# incandescentDriver.net
KiCad netlist of a schematic drawn in EAGLE
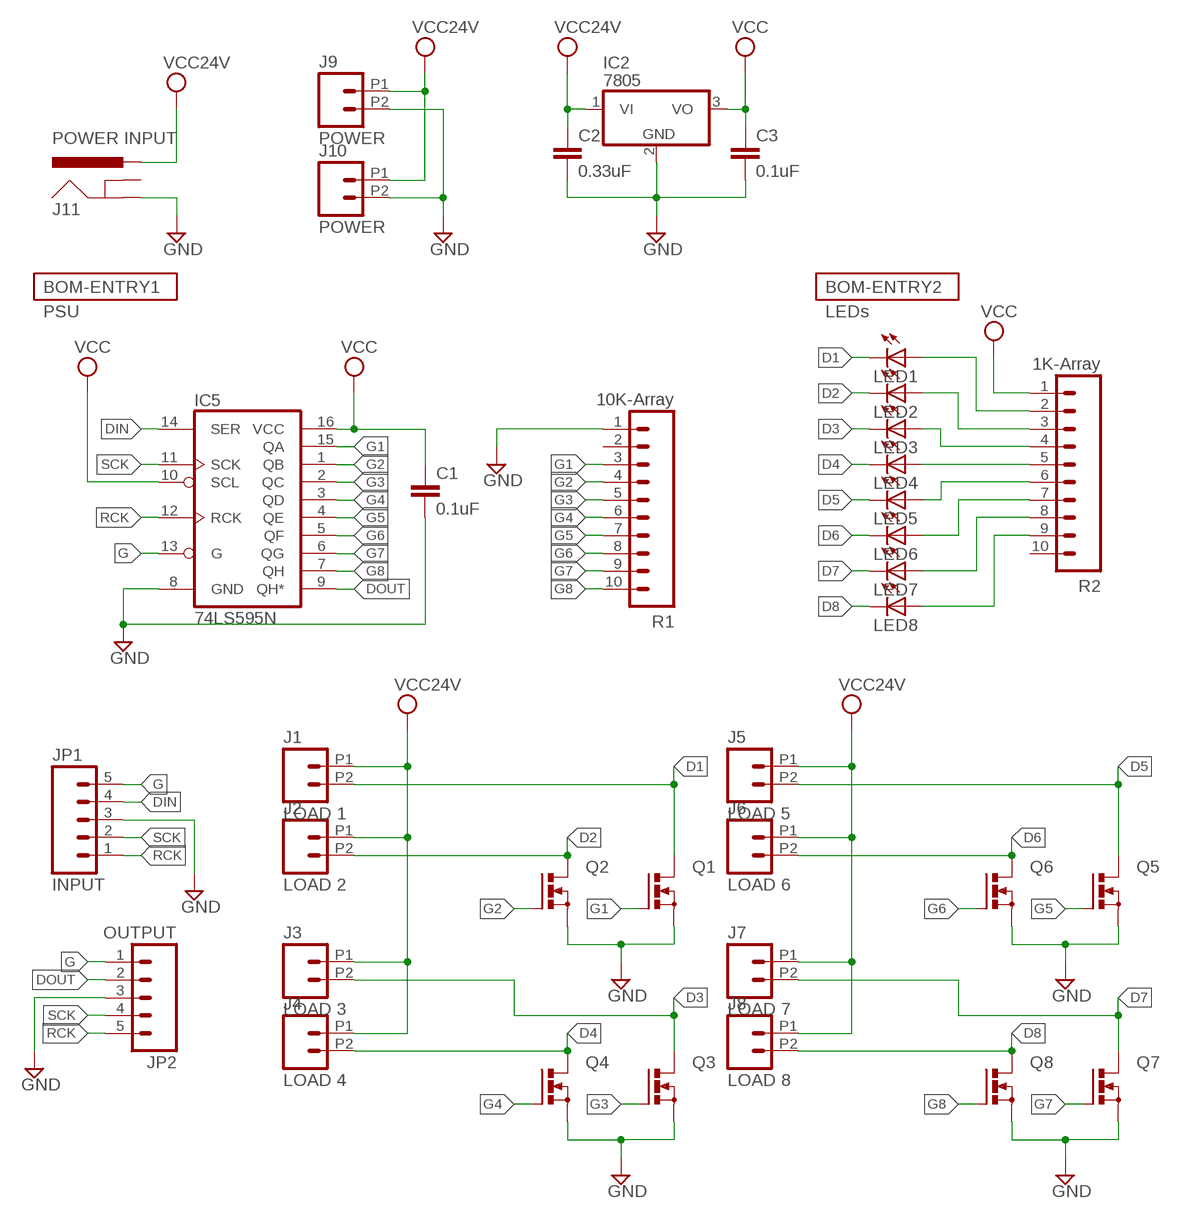
[diagram p0: schematic, sheet 1]

(export (version "E")
  (design (tool "Eeschema 10.0.6"))
  (components
    (comp (ref "C1")
      (value "0.1uF")
      (footprint "eagle-import:CAP-PTH-SMALL")
      (fields (field (name "PARTNO") "SR295E104MAR"))
      (libsource (lib "eagle-import") (part "CAPPTH"))
    )
    (comp (ref "C2")
      (value "0.33uF")
      (footprint "eagle-import:CAP-PTH-SMALL")
      (fields (field (name "PARTNO") "FK24X7R1H334K"))
      (libsource (lib "eagle-import") (part "CAPPTH"))
    )
    (comp (ref "C3")
      (value "0.1uF")
      (footprint "eagle-import:CAP-PTH-SMALL")
      (fields (field (name "PARTNO") "SR295E104MAR"))
      (libsource (lib "eagle-import") (part "CAPPTH"))
    )
    (comp (ref "IC2")
      (value "7805")
      (footprint "eagle-import:TO220V")
      (fields (field (name "PARTNO") "NCP7805TG"))
      (libsource (lib "eagle-import") (part "78TV8"))
    )
    (comp (ref "IC5")
      (value "74LS595N")
      (footprint "eagle-import:DIL16")
      (fields (field (name "PARTNO") "SN74HC164N"))
      (libsource (lib "eagle-import") (part "74595NLS"))
    )
    (comp (ref "J1")
      (value "LOAD 1")
      (footprint "eagle-import:1X02-5.08-SCREWTERM")
      (fields (field (name "PARTNO") "OSTTC022162"))
      (libsource (lib "eagle-import") (part "HEADER"))
    )
    (comp (ref "J2")
      (value "LOAD 2")
      (footprint "eagle-import:1X02-5.08-SCREWTERM")
      (fields (field (name "PARTNO") "OSTTC022162"))
      (libsource (lib "eagle-import") (part "HEADER"))
    )
    (comp (ref "J3")
      (value "LOAD 3")
      (footprint "eagle-import:1X02-5.08-SCREWTERM")
      (fields (field (name "PARTNO") "OSTTC022162"))
      (libsource (lib "eagle-import") (part "HEADER"))
    )
    (comp (ref "J4")
      (value "LOAD 4")
      (footprint "eagle-import:1X02-5.08-SCREWTERM")
      (fields (field (name "PARTNO") "OSTTC022162"))
      (libsource (lib "eagle-import") (part "HEADER"))
    )
    (comp (ref "J5")
      (value "LOAD 5")
      (footprint "eagle-import:1X02-5.08-SCREWTERM")
      (fields (field (name "PARTNO") "OSTTC022162"))
      (libsource (lib "eagle-import") (part "HEADER"))
    )
    (comp (ref "J6")
      (value "LOAD 6")
      (footprint "eagle-import:1X02-5.08-SCREWTERM")
      (fields (field (name "PARTNO") "OSTTC022162"))
      (libsource (lib "eagle-import") (part "HEADER"))
    )
    (comp (ref "J7")
      (value "LOAD 7")
      (footprint "eagle-import:1X02-5.08-SCREWTERM")
      (fields (field (name "PARTNO") "OSTTC022162"))
      (libsource (lib "eagle-import") (part "HEADER"))
    )
    (comp (ref "J8")
      (value "LOAD 8")
      (footprint "eagle-import:1X02-5.08-SCREWTERM")
      (fields (field (name "PARTNO") "OSTTC022162"))
      (libsource (lib "eagle-import") (part "HEADER"))
    )
    (comp (ref "J9")
      (value "POWER")
      (footprint "eagle-import:1X02-5.08-SCREWTERM")
      (fields (field (name "PARTNO") "OSTTC022162"))
      (libsource (lib "eagle-import") (part "HEADER"))
    )
    (comp (ref "J10")
      (value "POWER")
      (footprint "eagle-import:1X02-5.08-SCREWTERM")
      (fields (field (name "PARTNO") "OSTTC022162"))
      (libsource (lib "eagle-import") (part "HEADER"))
    )
    (comp (ref "J11")
      (value "POWER INPUT")
      (footprint "eagle-import:POWER_JACK_PTH_LOCK")
      (fields (field (name "PARTNO") "PJ-202A"))
      (libsource (lib "eagle-import") (part "POWER_JACKPTH_LOCK"))
    )
    (comp (ref "JP1")
      (value "INPUT")
      (footprint "eagle-import:1X05_LOCK")
      (fields (field (name "PARTNO") "M20-9960545"))
      (libsource (lib "eagle-import") (part "M05LOCK"))
    )
    (comp (ref "JP2")
      (value "OUTPUT")
      (footprint "eagle-import:1X05_LOCK")
      (fields (field (name "PARTNO") "M20-9960545"))
      (libsource (lib "eagle-import") (part "M05LOCK"))
    )
    (comp (ref "LED1")
      (value "LED5MM")
      (footprint "eagle-import:LED5MM")
      (libsource (lib "eagle-import") (part "LED5MM"))
    )
    (comp (ref "LED2")
      (value "LED5MM")
      (footprint "eagle-import:LED5MM")
      (libsource (lib "eagle-import") (part "LED5MM"))
    )
    (comp (ref "LED3")
      (value "LED5MM")
      (footprint "eagle-import:LED5MM")
      (libsource (lib "eagle-import") (part "LED5MM"))
    )
    (comp (ref "LED4")
      (value "LED5MM")
      (footprint "eagle-import:LED5MM")
      (libsource (lib "eagle-import") (part "LED5MM"))
    )
    (comp (ref "LED5")
      (value "LED5MM")
      (footprint "eagle-import:LED5MM")
      (libsource (lib "eagle-import") (part "LED5MM"))
    )
    (comp (ref "LED6")
      (value "LED5MM")
      (footprint "eagle-import:LED5MM")
      (libsource (lib "eagle-import") (part "LED5MM"))
    )
    (comp (ref "LED7")
      (value "LED5MM")
      (footprint "eagle-import:LED5MM")
      (libsource (lib "eagle-import") (part "LED5MM"))
    )
    (comp (ref "LED8")
      (value "LED5MM")
      (footprint "eagle-import:LED5MM")
      (libsource (lib "eagle-import") (part "LED5MM"))
    )
    (comp (ref "Q1")
      (value "PMOSFET_NTO220BV")
      (footprint "eagle-import:TO220BV")
      (fields (field (name "PARTNO") "FQP13N10L"))
      (libsource (lib "eagle-import") (part "PMOSFET_NTO220BV"))
    )
    (comp (ref "Q2")
      (value "PMOSFET_NTO220BV")
      (footprint "eagle-import:TO220BV")
      (fields (field (name "PARTNO") "FQP13N10L"))
      (libsource (lib "eagle-import") (part "PMOSFET_NTO220BV"))
    )
    (comp (ref "Q3")
      (value "PMOSFET_NTO220BV")
      (footprint "eagle-import:TO220BV")
      (fields (field (name "PARTNO") "FQP13N10L"))
      (libsource (lib "eagle-import") (part "PMOSFET_NTO220BV"))
    )
    (comp (ref "Q4")
      (value "PMOSFET_NTO220BV")
      (footprint "eagle-import:TO220BV")
      (fields (field (name "PARTNO") "FQP13N10L"))
      (libsource (lib "eagle-import") (part "PMOSFET_NTO220BV"))
    )
    (comp (ref "Q5")
      (value "PMOSFET_NTO220BV")
      (footprint "eagle-import:TO220BV")
      (fields (field (name "PARTNO") "FQP13N10L"))
      (libsource (lib "eagle-import") (part "PMOSFET_NTO220BV"))
    )
    (comp (ref "Q6")
      (value "PMOSFET_NTO220BV")
      (footprint "eagle-import:TO220BV")
      (fields (field (name "PARTNO") "FQP13N10L"))
      (libsource (lib "eagle-import") (part "PMOSFET_NTO220BV"))
    )
    (comp (ref "Q7")
      (value "PMOSFET_NTO220BV")
      (footprint "eagle-import:TO220BV")
      (fields (field (name "PARTNO") "FQP13N10L"))
      (libsource (lib "eagle-import") (part "PMOSFET_NTO220BV"))
    )
    (comp (ref "Q8")
      (value "PMOSFET_NTO220BV")
      (footprint "eagle-import:TO220BV")
      (fields (field (name "PARTNO") "FQP13N10L"))
      (libsource (lib "eagle-import") (part "PMOSFET_NTO220BV"))
    )
    (comp (ref "R1")
      (value "10K-Array")
      (footprint "eagle-import:1X10_LOCK")
      (fields (field (name "PARTNO") "L101S103LF"))
      (libsource (lib "eagle-import") (part "M10LOCK"))
    )
    (comp (ref "R2")
      (value "1K-Array")
      (footprint "eagle-import:1X10_LOCK")
      (fields (field (name "PARTNO") "4609X-101-102LF"))
      (libsource (lib "eagle-import") (part "M10LOCK"))
    )
  )
  (nets
    (net (code "1") (name "D1") (class "Default")
      (node (ref "J1") (pin "P2") (pinfunction "1_P2") (pintype "passive"))
      (node (ref "LED1") (pin "K") (pinfunction "C_K") (pintype "passive"))
      (node (ref "Q1") (pin "D") (pinfunction "D_D") (pintype "passive"))
    )
    (net (code "2") (name "D2") (class "Default")
      (node (ref "J2") (pin "P2") (pinfunction "1_P2") (pintype "passive"))
      (node (ref "LED2") (pin "K") (pinfunction "C_K") (pintype "passive"))
      (node (ref "Q2") (pin "D") (pinfunction "D_D") (pintype "passive"))
    )
    (net (code "3") (name "D3") (class "Default")
      (node (ref "J3") (pin "P2") (pinfunction "1_P2") (pintype "passive"))
      (node (ref "LED3") (pin "K") (pinfunction "C_K") (pintype "passive"))
      (node (ref "Q3") (pin "D") (pinfunction "D_D") (pintype "passive"))
    )
    (net (code "4") (name "D4") (class "Default")
      (node (ref "J4") (pin "P2") (pinfunction "1_P2") (pintype "passive"))
      (node (ref "LED4") (pin "K") (pinfunction "C_K") (pintype "passive"))
      (node (ref "Q4") (pin "D") (pinfunction "D_D") (pintype "passive"))
    )
    (net (code "5") (name "D5") (class "Default")
      (node (ref "J5") (pin "P2") (pinfunction "1_P2") (pintype "passive"))
      (node (ref "LED5") (pin "K") (pinfunction "C_K") (pintype "passive"))
      (node (ref "Q5") (pin "D") (pinfunction "D_D") (pintype "passive"))
    )
    (net (code "6") (name "D6") (class "Default")
      (node (ref "J6") (pin "P2") (pinfunction "1_P2") (pintype "passive"))
      (node (ref "LED6") (pin "K") (pinfunction "C_K") (pintype "passive"))
      (node (ref "Q6") (pin "D") (pinfunction "D_D") (pintype "passive"))
    )
    (net (code "7") (name "D7") (class "Default")
      (node (ref "J7") (pin "P2") (pinfunction "1_P2") (pintype "passive"))
      (node (ref "LED7") (pin "K") (pinfunction "C_K") (pintype "passive"))
      (node (ref "Q7") (pin "D") (pinfunction "D_D") (pintype "passive"))
    )
    (net (code "8") (name "D8") (class "Default")
      (node (ref "J8") (pin "P2") (pinfunction "1_P2") (pintype "passive"))
      (node (ref "LED8") (pin "K") (pinfunction "C_K") (pintype "passive"))
      (node (ref "Q8") (pin "D") (pinfunction "D_D") (pintype "passive"))
    )
    (net (code "9") (name "DIN") (class "Default")
      (node (ref "IC5") (pin "14") (pinfunction "SER_14") (pintype "input"))
      (node (ref "JP1") (pin "4") (pinfunction "4_4") (pintype "passive"))
    )
    (net (code "10") (name "DOUT") (class "Default")
      (node (ref "IC5") (pin "9") (pinfunction "QH*_9") (pintype "tri_state"))
      (node (ref "JP2") (pin "2") (pinfunction "2_2") (pintype "passive"))
    )
    (net (code "11") (name "G") (class "Default")
      (node (ref "IC5") (pin "13") (pinfunction "G_13") (pintype "input"))
      (node (ref "JP1") (pin "5") (pinfunction "5_5") (pintype "passive"))
      (node (ref "JP2") (pin "1") (pinfunction "1_1") (pintype "passive"))
    )
    (net (code "12") (name "G1") (class "Default")
      (node (ref "IC5") (pin "15") (pinfunction "QA_15") (pintype "tri_state"))
      (node (ref "Q1") (pin "G") (pinfunction "G_G") (pintype "passive"))
      (node (ref "R1") (pin "3") (pinfunction "3_3") (pintype "passive"))
    )
    (net (code "13") (name "G2") (class "Default")
      (node (ref "IC5") (pin "1") (pinfunction "QB_1") (pintype "tri_state"))
      (node (ref "Q2") (pin "G") (pinfunction "G_G") (pintype "passive"))
      (node (ref "R1") (pin "4") (pinfunction "4_4") (pintype "passive"))
    )
    (net (code "14") (name "G3") (class "Default")
      (node (ref "IC5") (pin "2") (pinfunction "QC_2") (pintype "tri_state"))
      (node (ref "Q3") (pin "G") (pinfunction "G_G") (pintype "passive"))
      (node (ref "R1") (pin "5") (pinfunction "5_5") (pintype "passive"))
    )
    (net (code "15") (name "G4") (class "Default")
      (node (ref "IC5") (pin "3") (pinfunction "QD_3") (pintype "tri_state"))
      (node (ref "Q4") (pin "G") (pinfunction "G_G") (pintype "passive"))
      (node (ref "R1") (pin "6") (pinfunction "6_6") (pintype "passive"))
    )
    (net (code "16") (name "G5") (class "Default")
      (node (ref "IC5") (pin "4") (pinfunction "QE_4") (pintype "tri_state"))
      (node (ref "Q5") (pin "G") (pinfunction "G_G") (pintype "passive"))
      (node (ref "R1") (pin "7") (pinfunction "7_7") (pintype "passive"))
    )
    (net (code "17") (name "G6") (class "Default")
      (node (ref "IC5") (pin "5") (pinfunction "QF_5") (pintype "tri_state"))
      (node (ref "Q6") (pin "G") (pinfunction "G_G") (pintype "passive"))
      (node (ref "R1") (pin "8") (pinfunction "8_8") (pintype "passive"))
    )
    (net (code "18") (name "G7") (class "Default")
      (node (ref "IC5") (pin "6") (pinfunction "QG_6") (pintype "tri_state"))
      (node (ref "Q7") (pin "G") (pinfunction "G_G") (pintype "passive"))
      (node (ref "R1") (pin "9") (pinfunction "9_9") (pintype "passive"))
    )
    (net (code "19") (name "G8") (class "Default")
      (node (ref "IC5") (pin "7") (pinfunction "QH_7") (pintype "tri_state"))
      (node (ref "Q8") (pin "G") (pinfunction "G_G") (pintype "passive"))
      (node (ref "R1") (pin "10") (pinfunction "10_10") (pintype "passive"))
    )
    (net (code "20") (name "GND") (class "Default")
      (node (ref "C1") (pin "2") (pinfunction "2_2") (pintype "passive"))
      (node (ref "C2") (pin "2") (pinfunction "2_2") (pintype "passive"))
      (node (ref "C3") (pin "2") (pinfunction "2_2") (pintype "passive"))
      (node (ref "IC2") (pin "2") (pinfunction "GND_2") (pintype "passive"))
      (node (ref "IC5") (pin "8") (pinfunction "GND_8") (pintype "power_in"))
      (node (ref "J10") (pin "P2") (pinfunction "1_P2") (pintype "passive"))
      (node (ref "J11") (pin "GND") (pinfunction "GND_GND") (pintype "bidirectional"))
      (node (ref "J9") (pin "P2") (pinfunction "1_P2") (pintype "passive"))
      (node (ref "JP1") (pin "3") (pinfunction "3_3") (pintype "passive"))
      (node (ref "JP2") (pin "3") (pinfunction "3_3") (pintype "passive"))
      (node (ref "Q1") (pin "S") (pinfunction "S_S") (pintype "passive"))
      (node (ref "Q2") (pin "S") (pinfunction "S_S") (pintype "passive"))
      (node (ref "Q3") (pin "S") (pinfunction "S_S") (pintype "passive"))
      (node (ref "Q4") (pin "S") (pinfunction "S_S") (pintype "passive"))
      (node (ref "Q5") (pin "S") (pinfunction "S_S") (pintype "passive"))
      (node (ref "Q6") (pin "S") (pinfunction "S_S") (pintype "passive"))
      (node (ref "Q7") (pin "S") (pinfunction "S_S") (pintype "passive"))
      (node (ref "Q8") (pin "S") (pinfunction "S_S") (pintype "passive"))
      (node (ref "R1") (pin "1") (pinfunction "1_1") (pintype "passive"))
    )
    (net (code "21") (name "Net-(LED1-PadA)") (class "Default")
      (node (ref "LED1") (pin "A") (pinfunction "A_A") (pintype "passive"))
      (node (ref "R2") (pin "2") (pinfunction "2_2") (pintype "passive"))
    )
    (net (code "22") (name "Net-(LED2-PadA)") (class "Default")
      (node (ref "LED2") (pin "A") (pinfunction "A_A") (pintype "passive"))
      (node (ref "R2") (pin "3") (pinfunction "3_3") (pintype "passive"))
    )
    (net (code "23") (name "Net-(LED3-PadA)") (class "Default")
      (node (ref "LED3") (pin "A") (pinfunction "A_A") (pintype "passive"))
      (node (ref "R2") (pin "4") (pinfunction "4_4") (pintype "passive"))
    )
    (net (code "24") (name "Net-(LED4-PadA)") (class "Default")
      (node (ref "LED4") (pin "A") (pinfunction "A_A") (pintype "passive"))
      (node (ref "R2") (pin "5") (pinfunction "5_5") (pintype "passive"))
    )
    (net (code "25") (name "Net-(LED5-PadA)") (class "Default")
      (node (ref "LED5") (pin "A") (pinfunction "A_A") (pintype "passive"))
      (node (ref "R2") (pin "6") (pinfunction "6_6") (pintype "passive"))
    )
    (net (code "26") (name "Net-(LED6-PadA)") (class "Default")
      (node (ref "LED6") (pin "A") (pinfunction "A_A") (pintype "passive"))
      (node (ref "R2") (pin "7") (pinfunction "7_7") (pintype "passive"))
    )
    (net (code "27") (name "Net-(LED7-PadA)") (class "Default")
      (node (ref "LED7") (pin "A") (pinfunction "A_A") (pintype "passive"))
      (node (ref "R2") (pin "8") (pinfunction "8_8") (pintype "passive"))
    )
    (net (code "28") (name "Net-(LED8-PadA)") (class "Default")
      (node (ref "LED8") (pin "A") (pinfunction "A_A") (pintype "passive"))
      (node (ref "R2") (pin "9") (pinfunction "9_9") (pintype "passive"))
    )
    (net (code "29") (name "RCK") (class "Default")
      (node (ref "IC5") (pin "12") (pinfunction "RCK_12") (pintype "input"))
      (node (ref "JP1") (pin "1") (pinfunction "1_1") (pintype "passive"))
      (node (ref "JP2") (pin "5") (pinfunction "5_5") (pintype "passive"))
    )
    (net (code "30") (name "SCK") (class "Default")
      (node (ref "IC5") (pin "11") (pinfunction "SCK_11") (pintype "input"))
      (node (ref "JP1") (pin "2") (pinfunction "2_2") (pintype "passive"))
      (node (ref "JP2") (pin "4") (pinfunction "4_4") (pintype "passive"))
    )
    (net (code "31") (name "VCC") (class "Default")
      (node (ref "C1") (pin "1") (pinfunction "1_1") (pintype "passive"))
      (node (ref "C3") (pin "1") (pinfunction "1_1") (pintype "passive"))
      (node (ref "IC2") (pin "3") (pinfunction "VO_3") (pintype "passive"))
      (node (ref "IC5") (pin "10") (pinfunction "SCL_10") (pintype "input"))
      (node (ref "IC5") (pin "16") (pinfunction "VCC_16") (pintype "power_in"))
      (node (ref "R2") (pin "1") (pinfunction "1_1") (pintype "passive"))
    )
    (net (code "32") (name "VCC24V") (class "Default")
      (node (ref "C2") (pin "1") (pinfunction "1_1") (pintype "passive"))
      (node (ref "IC2") (pin "1") (pinfunction "VI_1") (pintype "input"))
      (node (ref "J1") (pin "P1") (pinfunction "2_P1") (pintype "passive"))
      (node (ref "J10") (pin "P1") (pinfunction "2_P1") (pintype "passive"))
      (node (ref "J11") (pin "PWR") (pinfunction "PWR_PWR") (pintype "bidirectional"))
      (node (ref "J2") (pin "P1") (pinfunction "2_P1") (pintype "passive"))
      (node (ref "J3") (pin "P1") (pinfunction "2_P1") (pintype "passive"))
      (node (ref "J4") (pin "P1") (pinfunction "2_P1") (pintype "passive"))
      (node (ref "J5") (pin "P1") (pinfunction "2_P1") (pintype "passive"))
      (node (ref "J6") (pin "P1") (pinfunction "2_P1") (pintype "passive"))
      (node (ref "J7") (pin "P1") (pinfunction "2_P1") (pintype "passive"))
      (node (ref "J8") (pin "P1") (pinfunction "2_P1") (pintype "passive"))
      (node (ref "J9") (pin "P1") (pinfunction "2_P1") (pintype "passive"))
    )
    (net (code "33") (name "unconnected-(J11-PadGNDBREAK)") (class "Default")
      (node (ref "J11") (pin "GNDBREAK") (pinfunction "GNDBREAK_GNDBREAK") (pintype "bidirectional"))
    )
    (net (code "34") (name "unconnected-(R1-Pad2)") (class "Default")
      (node (ref "R1") (pin "2") (pinfunction "2_2") (pintype "passive"))
    )
    (net (code "35") (name "unconnected-(R2-Pad10)") (class "Default")
      (node (ref "R2") (pin "10") (pinfunction "10_10") (pintype "passive"))
    )
  )
)
